# Sheet1.net
KiCad netlist of a schematic drawn in Altium Designer
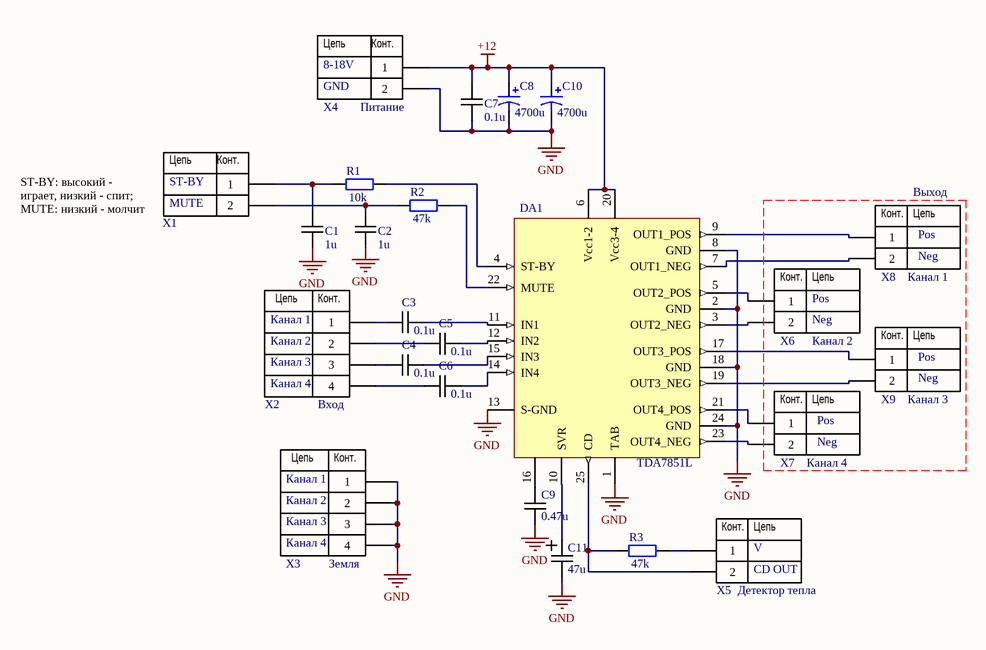
[diagram p0: Sheet1.SchDoc]

(export (version "E")
  (design (tool "Eeschema 10.0.6"))
  (components
    (comp (ref "C1")
      (value "1u")
      (footprint "Capacitor SMD 0805")
      (fields (field (name "Comment") "Cap"))
      (libsource (lib "Библиотека компонентов") (part "Cap"))
    )
    (comp (ref "C2")
      (value "1u")
      (footprint "Capacitor SMD 0805")
      (fields (field (name "Comment") "Cap"))
      (libsource (lib "Библиотека компонентов") (part "Cap"))
    )
    (comp (ref "C3")
      (value "0.1u")
      (footprint "Capacitor SMD 0805")
      (fields (field (name "Comment") "Cap"))
      (libsource (lib "Библиотека компонентов") (part "Cap"))
    )
    (comp (ref "C4")
      (value "0.1u")
      (footprint "Capacitor SMD 0805")
      (fields (field (name "Comment") "Cap"))
      (libsource (lib "Библиотека компонентов") (part "Cap"))
    )
    (comp (ref "C5")
      (value "0.1u")
      (footprint "Capacitor SMD 0805")
      (fields (field (name "Comment") "Cap"))
      (libsource (lib "Библиотека компонентов") (part "Cap"))
    )
    (comp (ref "C6")
      (value "0.1u")
      (footprint "Capacitor SMD 0805")
      (fields (field (name "Comment") "Cap"))
      (libsource (lib "Библиотека компонентов") (part "Cap"))
    )
    (comp (ref "C7")
      (value "0.1u")
      (footprint "Capacitor SMD 0805")
      (fields (field (name "Comment") "Cap"))
      (libsource (lib "Библиотека компонентов") (part "Cap"))
    )
    (comp (ref "C8")
      (value "4700u")
      (footprint "RB7.6-15")
      (description "Polarized Capacitor (Radial)")
      (fields (field (name "Comment") "Cap Pol1") (field (name "PUBLISHER") "Altium Limited"))
      (libsource (lib "Miscellaneous Devices") (part "Cap Pol1"))
    )
    (comp (ref "C9")
      (value "0.47u")
      (footprint "Capacitor SMD 0805")
      (fields (field (name "Comment") "Cap"))
      (libsource (lib "Библиотека компонентов") (part "Cap"))
    )
    (comp (ref "C10")
      (value "4700u")
      (footprint "RB7.6-15")
      (description "Polarized Capacitor (Radial)")
      (fields (field (name "Comment") "Cap Pol1") (field (name "PUBLISHER") "Altium Limited"))
      (libsource (lib "Miscellaneous Devices") (part "Cap Pol1"))
    )
    (comp (ref "C11")
      (value "47u")
      (footprint "Capacitor Polar Round 5mm")
      (fields (field (name "VOLTAGE") "16V") (field (name "Comment") "Cap Polar"))
      (libsource (lib "Библиотека компонентов") (part "Cap Polar"))
    )
    (comp (ref "DA1")
      (value "TDA7851L")
      (footprint "TDA7851L (Flexiwatt25)")
      (libsource (lib "Библиотека компонентов") (part "TDA7851L"))
    )
    (comp (ref "R1")
      (value "10k")
      (footprint "AXIAL-0.4")
      (description "Resistor")
      (fields (field (name "Comment") "Res2") (field (name "PUBLISHER") "Altium Limited"))
      (libsource (lib "Miscellaneous Devices") (part "Res2"))
    )
    (comp (ref "R2")
      (value "47k")
      (footprint "AXIAL-0.4")
      (description "Resistor")
      (fields (field (name "Comment") "Res2") (field (name "PUBLISHER") "Altium Limited"))
      (libsource (lib "Miscellaneous Devices") (part "Res2"))
    )
    (comp (ref "R3")
      (value "47k")
      (footprint "AXIAL-0.4")
      (description "Resistor")
      (fields (field (name "Comment") "Res2") (field (name "PUBLISHER") "Altium Limited"))
      (libsource (lib "Miscellaneous Devices") (part "Res2"))
    )
    (comp (ref "X1")
      (value "Header 2L")
      (footprint "Header 2")
      (libsource (lib "Библиотека компонентов") (part "Header 2L"))
    )
    (comp (ref "X2")
      (value "Header 4R")
      (footprint "Header 4")
      (libsource (lib "Библиотека компонентов") (part "Header 4R"))
    )
    (comp (ref "X3")
      (value "Header 4R")
      (footprint "Header 4")
      (libsource (lib "Библиотека компонентов") (part "Header 4R"))
    )
    (comp (ref "X4")
      (value "Header 2L")
      (footprint "Header 2")
      (libsource (lib "Библиотека компонентов") (part "Header 2L"))
    )
    (comp (ref "X5")
      (value "Header 2R")
      (footprint "Header 2")
      (libsource (lib "Библиотека компонентов") (part "Header 2R"))
    )
    (comp (ref "X6")
      (value "Header 2R")
      (footprint "Header 2")
      (libsource (lib "Библиотека компонентов") (part "Header 2R"))
    )
    (comp (ref "X7")
      (value "Header 2R")
      (footprint "Header 2")
      (libsource (lib "Библиотека компонентов") (part "Header 2R"))
    )
    (comp (ref "X8")
      (value "Header 2R")
      (footprint "Header 2")
      (libsource (lib "Библиотека компонентов") (part "Header 2R"))
    )
    (comp (ref "X9")
      (value "Header 2R")
      (footprint "Header 2")
      (libsource (lib "Библиотека компонентов") (part "Header 2R"))
    )
  )
  (nets
    (net (code "1") (name "+12") (class "Default")
      (node (ref "C10") (pin "1") (pinfunction "1_1") (pintype "passive"))
      (node (ref "C7") (pin "2") (pinfunction "2_2") (pintype "passive"))
      (node (ref "C8") (pin "1") (pinfunction "1_1") (pintype "passive"))
      (node (ref "DA1") (pin "20") (pinfunction "Vcc3-4_20") (pintype "power_in"))
      (node (ref "DA1") (pin "6") (pinfunction "Vcc1-2_6") (pintype "power_in"))
      (node (ref "X4") (pin "1") (pinfunction "1_1") (pintype "passive"))
    )
    (net (code "2") (name "GND") (class "Default")
      (node (ref "C1") (pin "2") (pinfunction "2_2") (pintype "passive"))
      (node (ref "C10") (pin "2") (pinfunction "2_2") (pintype "passive"))
      (node (ref "C11") (pin "2") (pinfunction "2_2") (pintype "passive"))
      (node (ref "C2") (pin "2") (pinfunction "2_2") (pintype "passive"))
      (node (ref "C7") (pin "1") (pinfunction "1_1") (pintype "passive"))
      (node (ref "C8") (pin "2") (pinfunction "2_2") (pintype "passive"))
      (node (ref "C9") (pin "1") (pinfunction "1_1") (pintype "passive"))
      (node (ref "DA1") (pin "1") (pinfunction "TAB_1") (pintype "power_in"))
      (node (ref "DA1") (pin "13") (pinfunction "S-GND_13") (pintype "power_in"))
      (node (ref "DA1") (pin "18") (pinfunction "GND_18") (pintype "power_in"))
      (node (ref "DA1") (pin "2") (pinfunction "GND_2") (pintype "power_in"))
      (node (ref "DA1") (pin "24") (pinfunction "GND_24") (pintype "power_in"))
      (node (ref "DA1") (pin "8") (pinfunction "GND_8") (pintype "power_in"))
      (node (ref "X3") (pin "1") (pinfunction "1_1") (pintype "passive"))
      (node (ref "X3") (pin "2") (pinfunction "2_2") (pintype "passive"))
      (node (ref "X3") (pin "3") (pinfunction "3_3") (pintype "passive"))
      (node (ref "X3") (pin "4") (pinfunction "4_4") (pintype "passive"))
      (node (ref "X4") (pin "2") (pinfunction "2_2") (pintype "passive"))
    )
    (net (code "3") (name "Net-(C1-Pad1)") (class "Default")
      (node (ref "C1") (pin "1") (pinfunction "1_1") (pintype "passive"))
      (node (ref "R1") (pin "1") (pinfunction "1_1") (pintype "passive"))
      (node (ref "X1") (pin "1") (pinfunction "1_1") (pintype "passive"))
    )
    (net (code "4") (name "Net-(C2-Pad1)") (class "Default")
      (node (ref "C2") (pin "1") (pinfunction "1_1") (pintype "passive"))
      (node (ref "R2") (pin "1") (pinfunction "1_1") (pintype "passive"))
      (node (ref "X1") (pin "2") (pinfunction "2_2") (pintype "passive"))
    )
    (net (code "5") (name "Net-(C3-Pad2)") (class "Default")
      (node (ref "C3") (pin "2") (pinfunction "2_2") (pintype "passive"))
      (node (ref "X2") (pin "1") (pinfunction "1_1") (pintype "passive"))
    )
    (net (code "6") (name "Net-(C4-Pad2)") (class "Default")
      (node (ref "C4") (pin "2") (pinfunction "2_2") (pintype "passive"))
      (node (ref "X2") (pin "3") (pinfunction "3_3") (pintype "passive"))
    )
    (net (code "7") (name "Net-(C5-Pad2)") (class "Default")
      (node (ref "C5") (pin "2") (pinfunction "2_2") (pintype "passive"))
      (node (ref "X2") (pin "2") (pinfunction "2_2") (pintype "passive"))
    )
    (net (code "8") (name "Net-(C6-Pad2)") (class "Default")
      (node (ref "C6") (pin "2") (pinfunction "2_2") (pintype "passive"))
      (node (ref "X2") (pin "4") (pinfunction "4_4") (pintype "passive"))
    )
    (net (code "9") (name "Net-(C9-Pad2)") (class "Default")
      (node (ref "C9") (pin "2") (pinfunction "2_2") (pintype "passive"))
      (node (ref "DA1") (pin "16") (pintype "power_in"))
    )
    (net (code "10") (name "Net-(DA1-CD)") (class "Default")
      (node (ref "DA1") (pin "25") (pinfunction "CD_25") (pintype "output"))
      (node (ref "R3") (pin "1") (pinfunction "1_1") (pintype "passive"))
      (node (ref "X5") (pin "2") (pinfunction "2_2") (pintype "passive"))
    )
    (net (code "11") (name "Net-(DA1-IN1)") (class "Default")
      (node (ref "C3") (pin "1") (pinfunction "1_1") (pintype "passive"))
      (node (ref "DA1") (pin "11") (pinfunction "IN1_11") (pintype "input"))
    )
    (net (code "12") (name "Net-(DA1-IN2)") (class "Default")
      (node (ref "C5") (pin "1") (pinfunction "1_1") (pintype "passive"))
      (node (ref "DA1") (pin "12") (pinfunction "IN2_12") (pintype "input"))
    )
    (net (code "13") (name "Net-(DA1-IN3)") (class "Default")
      (node (ref "C4") (pin "1") (pinfunction "1_1") (pintype "passive"))
      (node (ref "DA1") (pin "15") (pinfunction "IN3_15") (pintype "input"))
    )
    (net (code "14") (name "Net-(DA1-IN4)") (class "Default")
      (node (ref "C6") (pin "1") (pinfunction "1_1") (pintype "passive"))
      (node (ref "DA1") (pin "14") (pinfunction "IN4_14") (pintype "input"))
    )
    (net (code "15") (name "Net-(DA1-MUTE)") (class "Default")
      (node (ref "DA1") (pin "22") (pinfunction "MUTE_22") (pintype "input"))
      (node (ref "R2") (pin "2") (pinfunction "2_2") (pintype "passive"))
    )
    (net (code "16") (name "Net-(DA1-OUT1_NEG)") (class "Default")
      (node (ref "DA1") (pin "7") (pinfunction "OUT1_NEG_7") (pintype "output"))
      (node (ref "X8") (pin "2") (pinfunction "2_2") (pintype "passive"))
    )
    (net (code "17") (name "Net-(DA1-OUT1_POS)") (class "Default")
      (node (ref "DA1") (pin "9") (pinfunction "OUT1_POS_9") (pintype "output"))
      (node (ref "X8") (pin "1") (pinfunction "1_1") (pintype "passive"))
    )
    (net (code "18") (name "Net-(DA1-OUT2_NEG)") (class "Default")
      (node (ref "DA1") (pin "3") (pinfunction "OUT2_NEG_3") (pintype "output"))
      (node (ref "X6") (pin "2") (pinfunction "2_2") (pintype "passive"))
    )
    (net (code "19") (name "Net-(DA1-OUT2_POS)") (class "Default")
      (node (ref "DA1") (pin "5") (pinfunction "OUT2_POS_5") (pintype "output"))
      (node (ref "X6") (pin "1") (pinfunction "1_1") (pintype "passive"))
    )
    (net (code "20") (name "Net-(DA1-OUT3_NEG)") (class "Default")
      (node (ref "DA1") (pin "19") (pinfunction "OUT3_NEG_19") (pintype "output"))
      (node (ref "X9") (pin "2") (pinfunction "2_2") (pintype "passive"))
    )
    (net (code "21") (name "Net-(DA1-OUT3_POS)") (class "Default")
      (node (ref "DA1") (pin "17") (pinfunction "OUT3_POS_17") (pintype "output"))
      (node (ref "X9") (pin "1") (pinfunction "1_1") (pintype "passive"))
    )
    (net (code "22") (name "Net-(DA1-OUT4_NEG)") (class "Default")
      (node (ref "DA1") (pin "23") (pinfunction "OUT4_NEG_23") (pintype "output"))
      (node (ref "X7") (pin "2") (pinfunction "2_2") (pintype "passive"))
    )
    (net (code "23") (name "Net-(DA1-OUT4_POS)") (class "Default")
      (node (ref "DA1") (pin "21") (pinfunction "OUT4_POS_21") (pintype "output"))
      (node (ref "X7") (pin "1") (pinfunction "1_1") (pintype "passive"))
    )
    (net (code "24") (name "Net-(DA1-ST-BY)") (class "Default")
      (node (ref "DA1") (pin "4") (pinfunction "ST-BY_4") (pintype "input"))
      (node (ref "R1") (pin "2") (pinfunction "2_2") (pintype "passive"))
    )
    (net (code "25") (name "Net-(DA1-SVR)") (class "Default")
      (node (ref "C11") (pin "1") (pinfunction "1_1") (pintype "passive"))
      (node (ref "DA1") (pin "10") (pinfunction "SVR_10") (pintype "power_in"))
    )
    (net (code "26") (name "Net-(R3-Pad2)") (class "Default")
      (node (ref "R3") (pin "2") (pinfunction "2_2") (pintype "passive"))
      (node (ref "X5") (pin "1") (pinfunction "1_1") (pintype "passive"))
    )
  )
)
